# switch_2021-06-01.net
KiCad netlist of a schematic drawn in EasyEDA
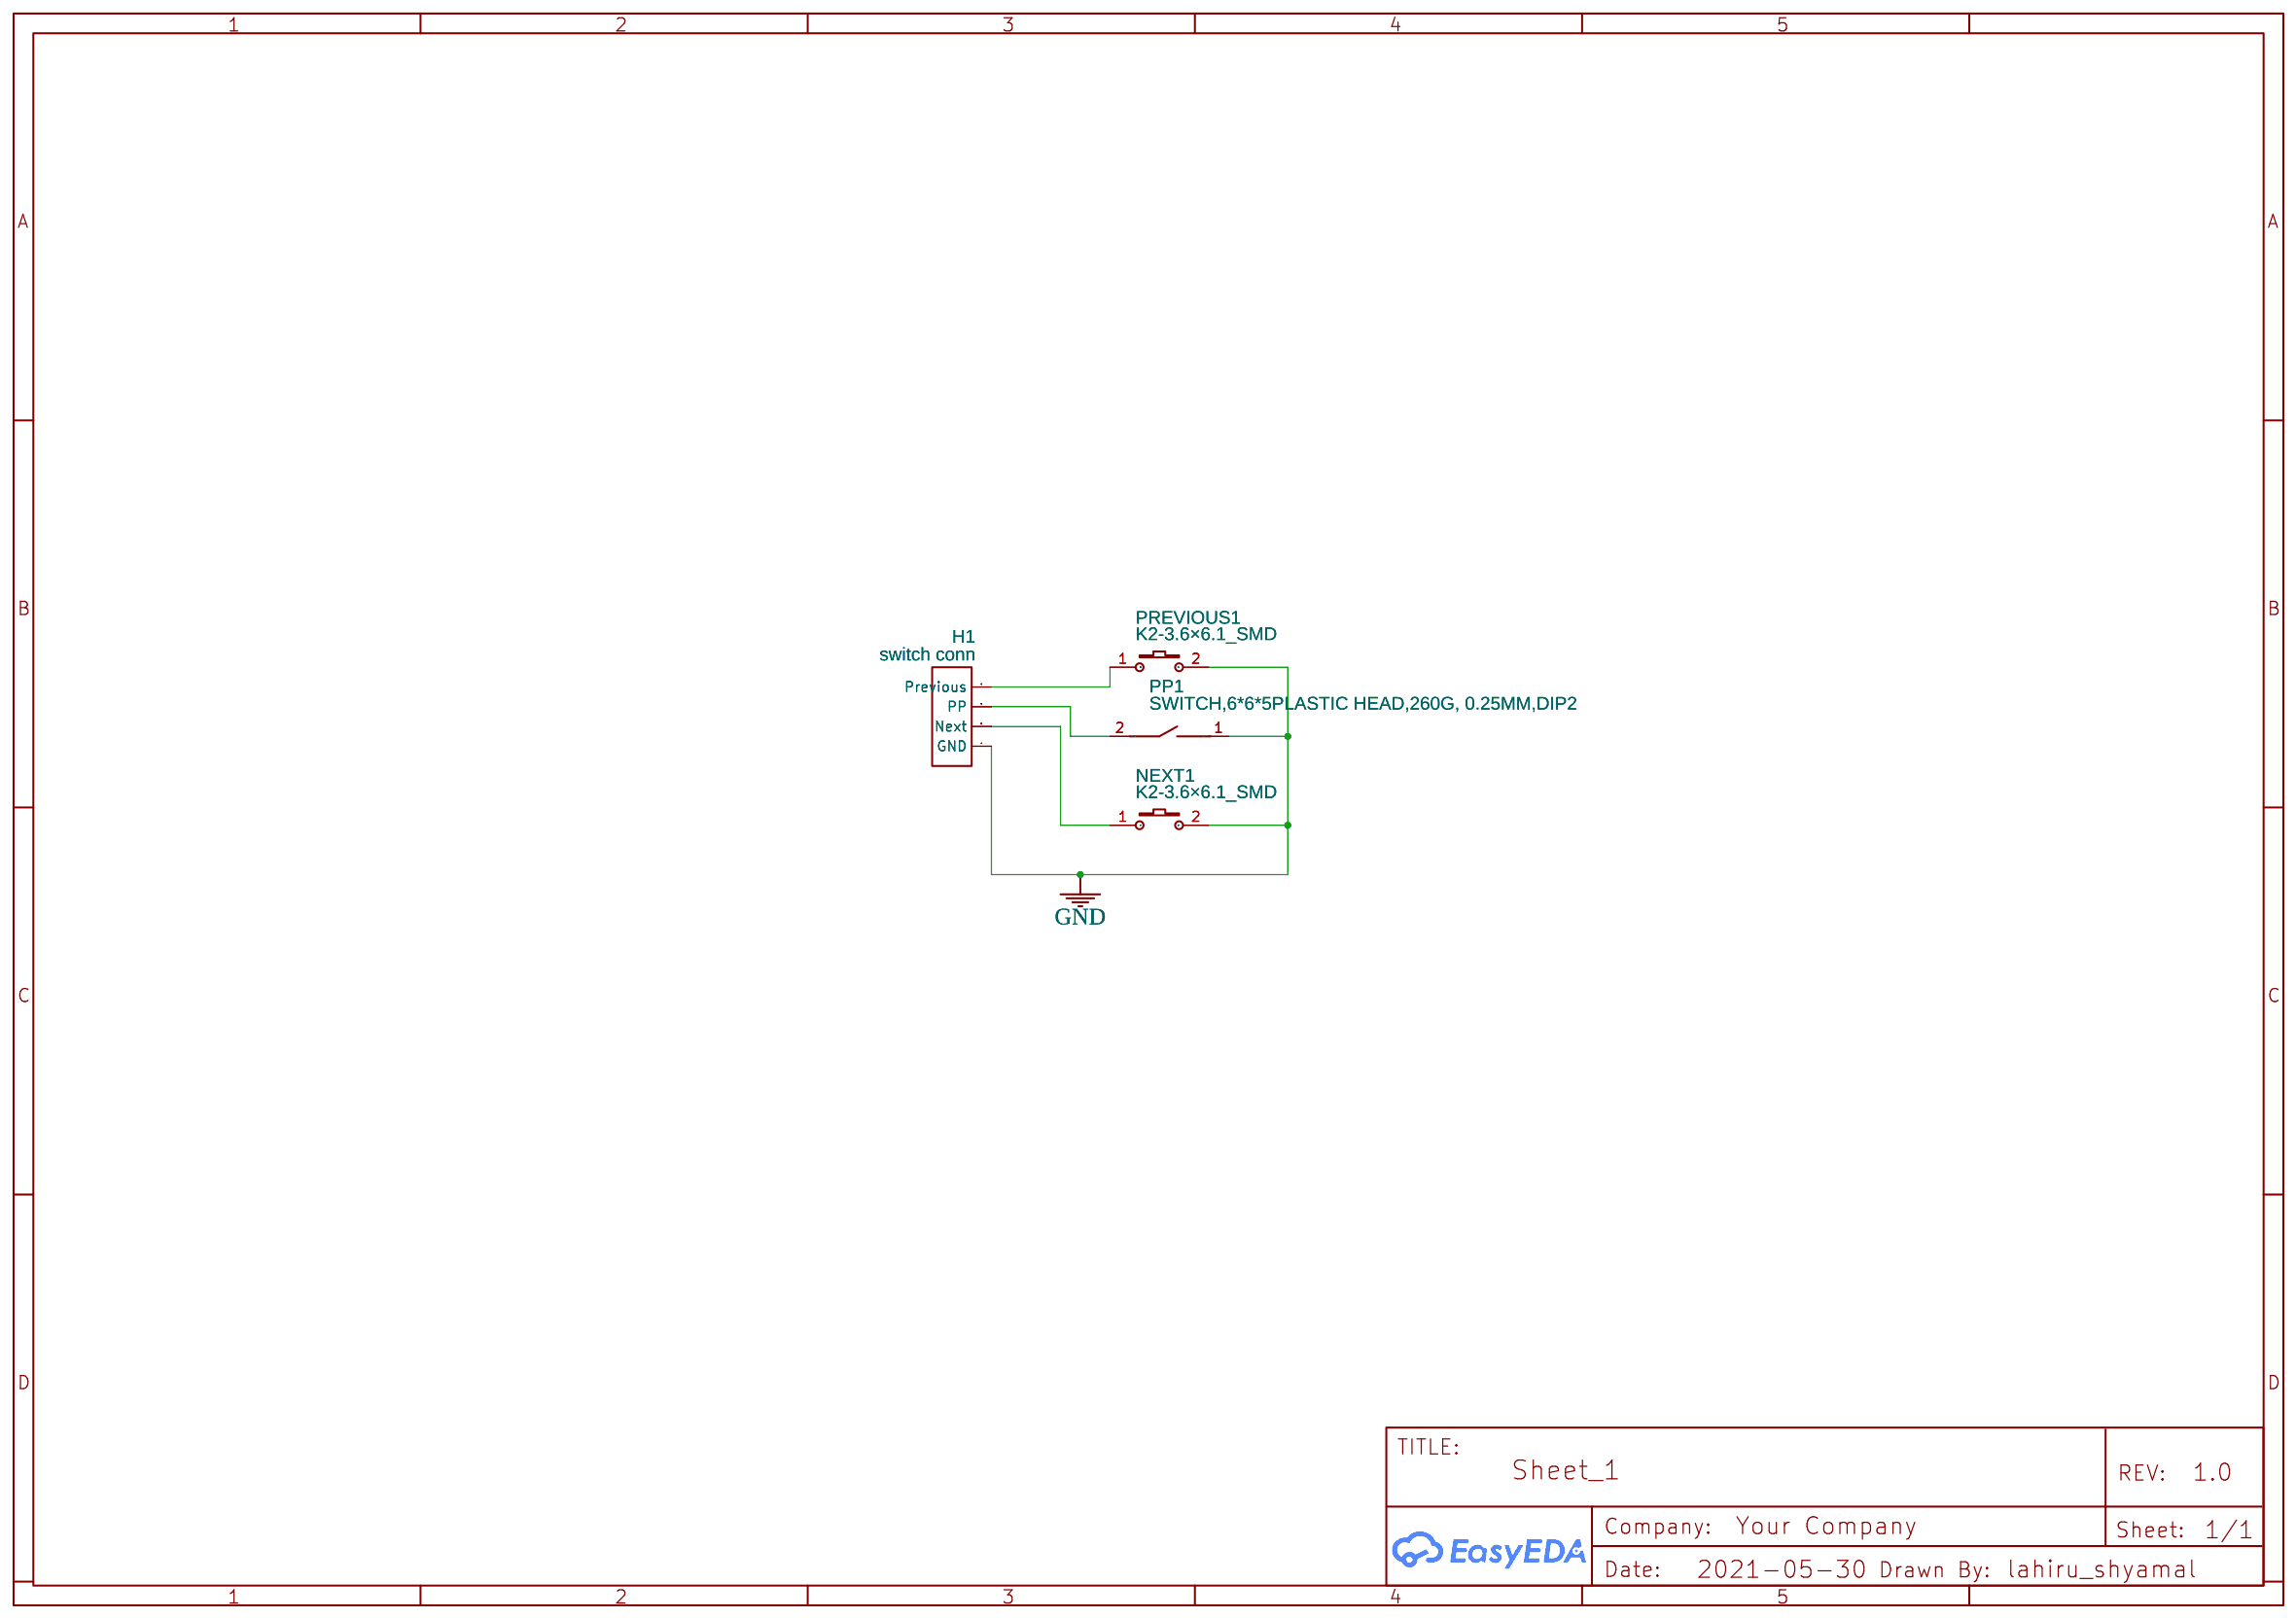
[diagram p0: schematic sheet]

(export (version "E")
  (design (tool "Eeschema 10.0.6"))
  (components
    (comp (ref "H1")
      (value "switch conn")
      (fields (field (name "BOM_Supplier Part") "C225501"))
      (libsource (lib "") (part "HDR-F-2.54_1x4"))
    )
    (comp (ref "NEXT1")
      (value "K2-3.6×6.1_SMD")
      (fields
        (field (name "BOM_Manufacturer Part") "K2-1107ST-A4SW-06")
        (field (name "BOM_Supplier Part") "C118141")
      )
      (libsource (lib "") (part "K2-3.6×6.1_SMD_1"))
    )
    (comp (ref "PP1")
      (value "SWITCH,6*6*5PLASTIC HEAD,260G, 0.25MM,DIP2")
      (fields
        (field (name "BOM_Manufacturer Part") "Switch,6*6*5Plastic head,260G, 0.25mm,DIP2")
        (field (name "BOM_Supplier Part") "C71845")
      )
      (libsource (lib "") (part "SWITCH,6*6*5PLASTIC HEAD,260G, 0.25MM,DIP2"))
    )
    (comp (ref "PREVIOUS1")
      (value "K2-3.6×6.1_SMD")
      (fields
        (field (name "BOM_Manufacturer Part") "K2-1107ST-A4SW-06")
        (field (name "BOM_Supplier Part") "C118141")
      )
      (libsource (lib "") (part "K2-3.6×6.1_SMD"))
    )
  )
  (nets
    (net (code "1") (name "GND") (class "Default")
      (node (ref "H1") (pin "4") (pinfunction "GND_4") (pintype "unspecified"))
      (node (ref "NEXT1") (pin "2") (pinfunction "2_2") (pintype "unspecified"))
      (node (ref "PP1") (pin "1") (pinfunction "1_1") (pintype "unspecified"))
      (node (ref "PREVIOUS1") (pin "2") (pinfunction "2_2") (pintype "unspecified"))
    )
    (net (code "2") (name "Net-(H1-Next)") (class "Default")
      (node (ref "H1") (pin "3") (pinfunction "Next_3") (pintype "unspecified"))
      (node (ref "NEXT1") (pin "1") (pinfunction "1_1") (pintype "unspecified"))
    )
    (net (code "3") (name "Net-(H1-PP)") (class "Default")
      (node (ref "H1") (pin "2") (pinfunction "PP_2") (pintype "unspecified"))
      (node (ref "PP1") (pin "2") (pinfunction "2_2") (pintype "unspecified"))
    )
    (net (code "4") (name "Net-(H1-Previous)") (class "Default")
      (node (ref "H1") (pin "1") (pinfunction "Previous_1") (pintype "unspecified"))
      (node (ref "PREVIOUS1") (pin "1") (pinfunction "1_1") (pintype "unspecified"))
    )
  )
)
